# RS232_HCPL2730.net
KiCad netlist of a schematic drawn in EAGLE
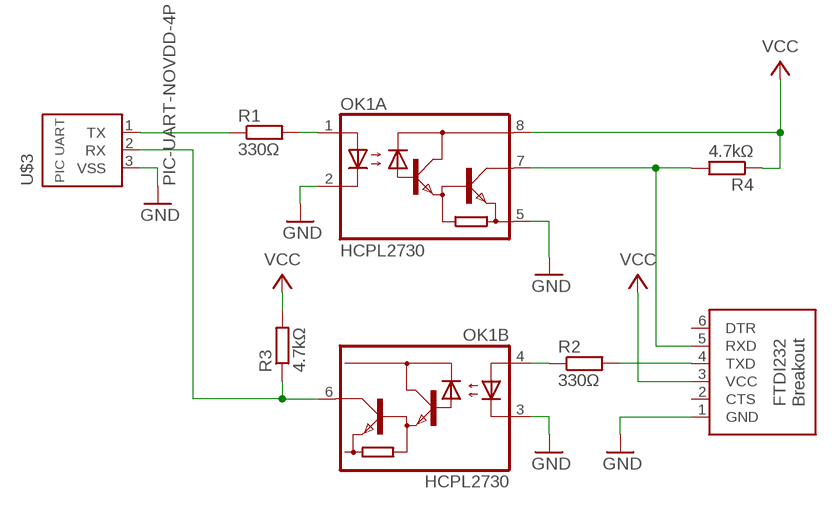
[diagram p0: schematic, sheet 1]

(export (version "E")
  (design (tool "Eeschema 10.0.6"))
  (components
    (comp (ref "OK1")
      (value "HCPL2730")
      (footprint "eagle-import:DIL08")
      (fields (field (name "MF") "AGILENT TECHNOLOGIES") (field (name "MPN") "HCPL-2730-000E"))
      (libsource (lib "eagle-import") (part "HCPL2730"))
    )
    (comp (ref "R1")
      (value "330Ω")
      (footprint "eagle-import:0207_10")
      (libsource (lib "eagle-import") (part "R-EU_0207/10"))
    )
    (comp (ref "R2")
      (value "330Ω")
      (footprint "eagle-import:0204_7")
      (libsource (lib "eagle-import") (part "R-EU_0204/7"))
    )
    (comp (ref "R3")
      (value "4.7kΩ")
      (footprint "eagle-import:0204_7")
      (libsource (lib "eagle-import") (part "R-EU_0204/7"))
    )
    (comp (ref "R4")
      (value "4.7kΩ")
      (footprint "eagle-import:0204_7")
      (libsource (lib "eagle-import") (part "R-EU_0204/7"))
    )
    (comp (ref "U$2")
      (value "FTDI232-BO-6P")
      (footprint "eagle-import:CONN-6P")
      (libsource (lib "eagle-import") (part "FTDI232-BO-6P"))
    )
    (comp (ref "U$3")
      (value "PIC-UART-NOVDD-4P")
      (footprint "eagle-import:CONN-4P")
      (libsource (lib "eagle-import") (part "PIC-UART-NOVDD-4P"))
    )
  )
  (nets
    (net (code "1") (name "GND") (class "Default")
      (node (ref "OK1") (pin "2") (pinfunction "C1_2") (pintype "passive"))
      (node (ref "OK1") (pin "3") (pinfunction "C2_3") (pintype "passive"))
      (node (ref "OK1") (pin "5") (pinfunction "GND_5") (pintype "passive"))
      (node (ref "U$2") (pin "1") (pinfunction "GND_1") (pintype "bidirectional"))
      (node (ref "U$3") (pin "3") (pinfunction "VSS_3") (pintype "bidirectional"))
    )
    (net (code "2") (name "Net-(OK1A-A1)") (class "Default")
      (node (ref "OK1") (pin "1") (pinfunction "A1_1") (pintype "passive"))
      (node (ref "R1") (pin "2") (pinfunction "2_2") (pintype "passive"))
    )
    (net (code "3") (name "Net-(OK1A-VO1)") (class "Default")
      (node (ref "OK1") (pin "7") (pinfunction "VO1_7") (pintype "passive"))
      (node (ref "R4") (pin "2") (pinfunction "2_2") (pintype "passive"))
      (node (ref "U$2") (pin "5") (pinfunction "RXD_5") (pintype "bidirectional"))
    )
    (net (code "4") (name "Net-(OK1B-A2)") (class "Default")
      (node (ref "OK1") (pin "4") (pinfunction "A2_4") (pintype "passive"))
      (node (ref "R2") (pin "1") (pinfunction "1_1") (pintype "passive"))
    )
    (net (code "5") (name "Net-(OK1B-VO2)") (class "Default")
      (node (ref "OK1") (pin "6") (pinfunction "VO2_6") (pintype "passive"))
      (node (ref "R3") (pin "1") (pinfunction "1_1") (pintype "passive"))
      (node (ref "U$3") (pin "2") (pinfunction "RX_2") (pintype "bidirectional"))
    )
    (net (code "6") (name "Net-(U$2-TXD)") (class "Default")
      (node (ref "R2") (pin "2") (pinfunction "2_2") (pintype "passive"))
      (node (ref "U$2") (pin "4") (pinfunction "TXD_4") (pintype "bidirectional"))
    )
    (net (code "7") (name "Net-(U$3-TX)") (class "Default")
      (node (ref "R1") (pin "1") (pinfunction "1_1") (pintype "passive"))
      (node (ref "U$3") (pin "1") (pinfunction "TX_1") (pintype "bidirectional"))
    )
    (net (code "8") (name "VCC") (class "Default")
      (node (ref "OK1") (pin "8") (pinfunction "VCC_8") (pintype "passive"))
      (node (ref "R3") (pin "2") (pinfunction "2_2") (pintype "passive"))
      (node (ref "R4") (pin "1") (pinfunction "1_1") (pintype "passive"))
      (node (ref "U$2") (pin "3") (pinfunction "VCC_3") (pintype "bidirectional"))
    )
    (net (code "9") (name "unconnected-(U$2-CTS-Pad2)") (class "Default")
      (node (ref "U$2") (pin "2") (pinfunction "CTS_2") (pintype "bidirectional"))
    )
    (net (code "10") (name "unconnected-(U$2-DTR-Pad6)") (class "Default")
      (node (ref "U$2") (pin "6") (pinfunction "DTR_6") (pintype "bidirectional"))
    )
  )
)
